# RELAYS.net
KiCad netlist of a schematic drawn in Altium Designer
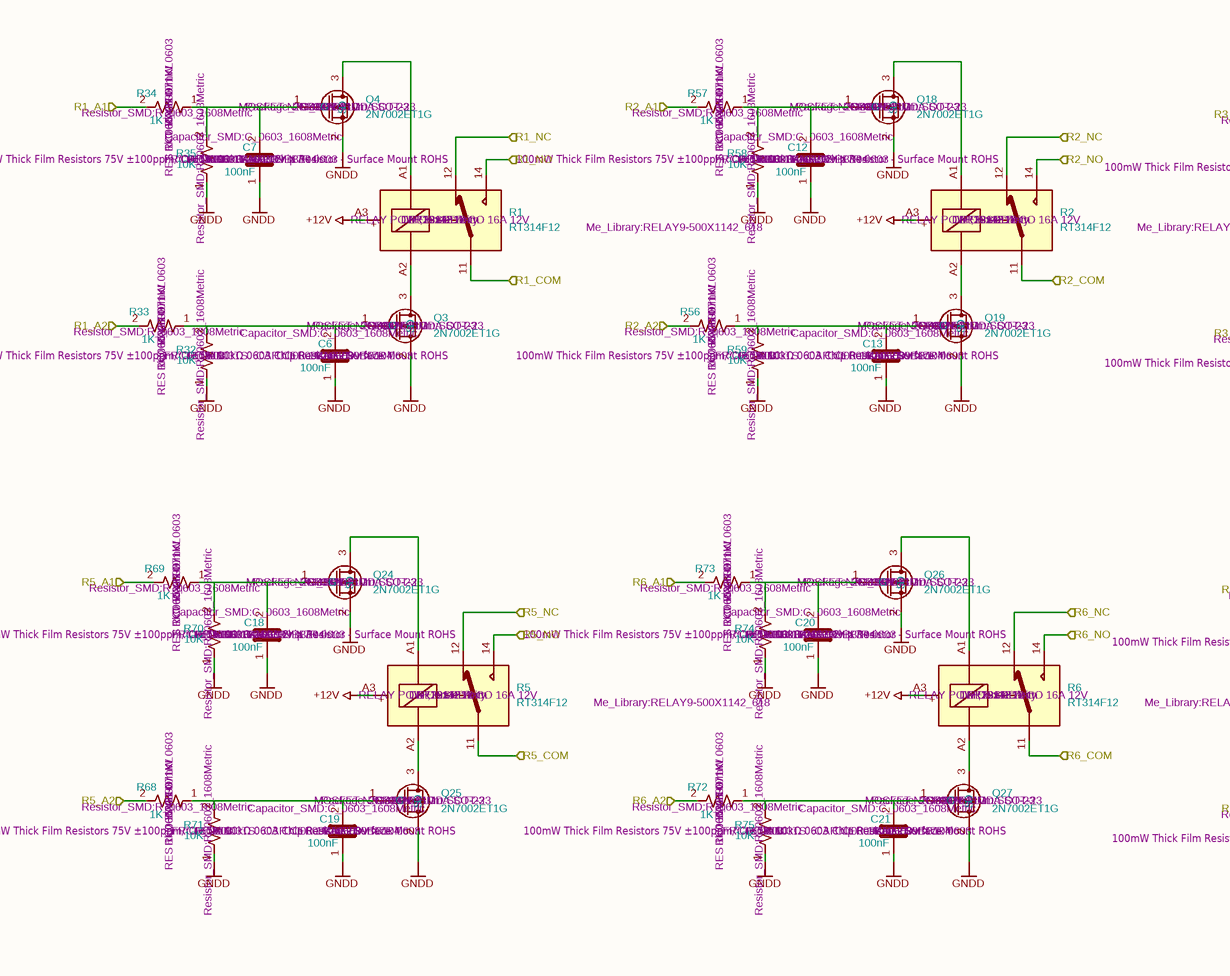
[diagram p0: RELAYS.SchDoc, left]
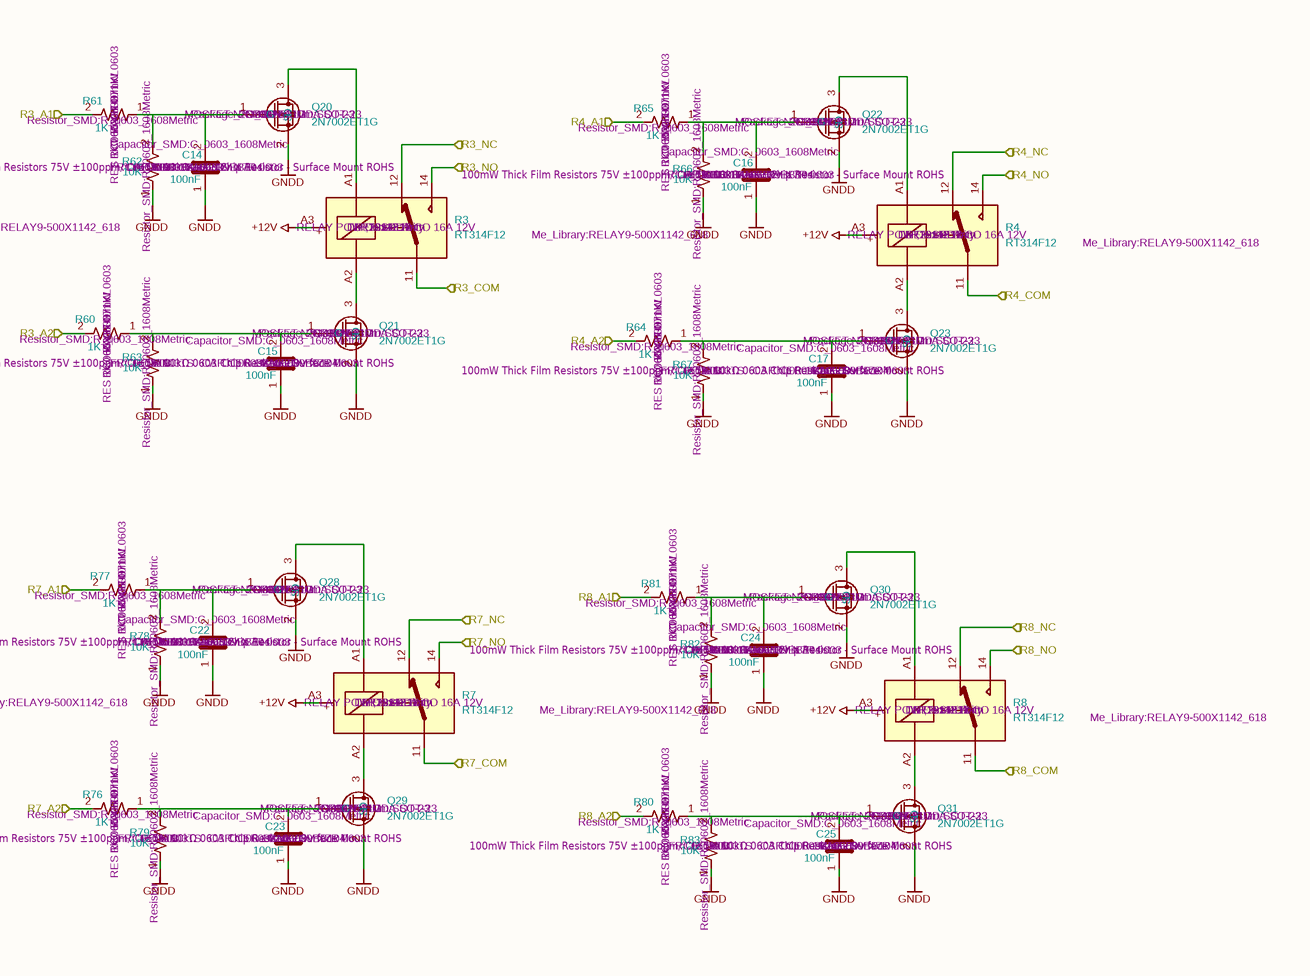
[diagram p1: RELAYS.SchDoc, right]

(export (version "E")
  (design (tool "Eeschema 10.0.6"))
  (components
    (comp (ref "C6")
      (value "100nF")
      (footprint "Capacitor_SMD:C_0603_1608Metric")
      (description "CAP CER 100nF 50V X7R 0603")
      (fields
        (field (name "MP") "CC0603KRX7R9BB104")
        (field (name "MF") "YAGEO")
        (field (name "PACKAGE") "C_0603")
      )
      (libsource (lib "*") (part "C_3"))
    )
    (comp (ref "C7")
      (value "100nF")
      (footprint "Capacitor_SMD:C_0603_1608Metric")
      (description "CAP CER 100nF 50V X7R 0603")
      (fields
        (field (name "MP") "CC0603KRX7R9BB104")
        (field (name "MF") "YAGEO")
        (field (name "PACKAGE") "C_0603")
      )
      (libsource (lib "*") (part "C_3"))
    )
    (comp (ref "C12")
      (value "100nF")
      (footprint "Capacitor_SMD:C_0603_1608Metric")
      (description "CAP CER 100nF 50V X7R 0603")
      (fields
        (field (name "MP") "CC0603KRX7R9BB104")
        (field (name "MF") "YAGEO")
        (field (name "PACKAGE") "C_0603")
      )
      (libsource (lib "*") (part "C_3"))
    )
    (comp (ref "C13")
      (value "100nF")
      (footprint "Capacitor_SMD:C_0603_1608Metric")
      (description "CAP CER 100nF 50V X7R 0603")
      (fields
        (field (name "MP") "CC0603KRX7R9BB104")
        (field (name "MF") "YAGEO")
        (field (name "PACKAGE") "C_0603")
      )
      (libsource (lib "*") (part "C_3"))
    )
    (comp (ref "C14")
      (value "100nF")
      (footprint "Capacitor_SMD:C_0603_1608Metric")
      (description "CAP CER 100nF 50V X7R 0603")
      (fields
        (field (name "MP") "CC0603KRX7R9BB104")
        (field (name "MF") "YAGEO")
        (field (name "PACKAGE") "C_0603")
      )
      (libsource (lib "*") (part "C_3"))
    )
    (comp (ref "C15")
      (value "100nF")
      (footprint "Capacitor_SMD:C_0603_1608Metric")
      (description "CAP CER 100nF 50V X7R 0603")
      (fields
        (field (name "MP") "CC0603KRX7R9BB104")
        (field (name "MF") "YAGEO")
        (field (name "PACKAGE") "C_0603")
      )
      (libsource (lib "*") (part "C_3"))
    )
    (comp (ref "C16")
      (value "100nF")
      (footprint "Capacitor_SMD:C_0603_1608Metric")
      (description "CAP CER 100nF 50V X7R 0603")
      (fields
        (field (name "MP") "CC0603KRX7R9BB104")
        (field (name "MF") "YAGEO")
        (field (name "PACKAGE") "C_0603")
      )
      (libsource (lib "*") (part "C_3"))
    )
    (comp (ref "C17")
      (value "100nF")
      (footprint "Capacitor_SMD:C_0603_1608Metric")
      (description "CAP CER 100nF 50V X7R 0603")
      (fields
        (field (name "MP") "CC0603KRX7R9BB104")
        (field (name "MF") "YAGEO")
        (field (name "PACKAGE") "C_0603")
      )
      (libsource (lib "*") (part "C_3"))
    )
    (comp (ref "C18")
      (value "100nF")
      (footprint "Capacitor_SMD:C_0603_1608Metric")
      (description "CAP CER 100nF 50V X7R 0603")
      (fields
        (field (name "MP") "CC0603KRX7R9BB104")
        (field (name "MF") "YAGEO")
        (field (name "PACKAGE") "C_0603")
      )
      (libsource (lib "*") (part "C_3"))
    )
    (comp (ref "C19")
      (value "100nF")
      (footprint "Capacitor_SMD:C_0603_1608Metric")
      (description "CAP CER 100nF 50V X7R 0603")
      (fields
        (field (name "MP") "CC0603KRX7R9BB104")
        (field (name "MF") "YAGEO")
        (field (name "PACKAGE") "C_0603")
      )
      (libsource (lib "*") (part "C_3"))
    )
    (comp (ref "C20")
      (value "100nF")
      (footprint "Capacitor_SMD:C_0603_1608Metric")
      (description "CAP CER 100nF 50V X7R 0603")
      (fields
        (field (name "MP") "CC0603KRX7R9BB104")
        (field (name "MF") "YAGEO")
        (field (name "PACKAGE") "C_0603")
      )
      (libsource (lib "*") (part "C_3"))
    )
    (comp (ref "C21")
      (value "100nF")
      (footprint "Capacitor_SMD:C_0603_1608Metric")
      (description "CAP CER 100nF 50V X7R 0603")
      (fields
        (field (name "MP") "CC0603KRX7R9BB104")
        (field (name "MF") "YAGEO")
        (field (name "PACKAGE") "C_0603")
      )
      (libsource (lib "*") (part "C_3"))
    )
    (comp (ref "C22")
      (value "100nF")
      (footprint "Capacitor_SMD:C_0603_1608Metric")
      (description "CAP CER 100nF 50V X7R 0603")
      (fields
        (field (name "MP") "CC0603KRX7R9BB104")
        (field (name "MF") "YAGEO")
        (field (name "PACKAGE") "C_0603")
      )
      (libsource (lib "*") (part "C_3"))
    )
    (comp (ref "C23")
      (value "100nF")
      (footprint "Capacitor_SMD:C_0603_1608Metric")
      (description "CAP CER 100nF 50V X7R 0603")
      (fields
        (field (name "MP") "CC0603KRX7R9BB104")
        (field (name "MF") "YAGEO")
        (field (name "PACKAGE") "C_0603")
      )
      (libsource (lib "*") (part "C_3"))
    )
    (comp (ref "C24")
      (value "100nF")
      (footprint "Capacitor_SMD:C_0603_1608Metric")
      (description "CAP CER 100nF 50V X7R 0603")
      (fields
        (field (name "MP") "CC0603KRX7R9BB104")
        (field (name "MF") "YAGEO")
        (field (name "PACKAGE") "C_0603")
      )
      (libsource (lib "*") (part "C_3"))
    )
    (comp (ref "C25")
      (value "100nF")
      (footprint "Capacitor_SMD:C_0603_1608Metric")
      (description "CAP CER 100nF 50V X7R 0603")
      (fields
        (field (name "MP") "CC0603KRX7R9BB104")
        (field (name "MF") "YAGEO")
        (field (name "PACKAGE") "C_0603")
      )
      (libsource (lib "*") (part "C_3"))
    )
    (comp (ref "Q3")
      (value "2N7002ET1G")
      (footprint "Package_TO_SOT_SMD:SOT-23")
      (description "MOSFET N-CH 60V 310mA SOT-23")
      (fields
        (field (name "MP") "2N7002ET1G")
        (field (name "MF") "onsemi")
        (field (name "PACKAGE") "SOT-23")
        (field (name "OZD") "2N7002ET1G")
      )
      (libsource (lib "Transistor_FET_Other") (part "Q_NMOS_Depletion_GSD"))
    )
    (comp (ref "Q4")
      (value "2N7002ET1G")
      (footprint "Package_TO_SOT_SMD:SOT-23")
      (description "MOSFET N-CH 60V 310mA SOT-23")
      (fields
        (field (name "MP") "2N7002ET1G")
        (field (name "MF") "onsemi")
        (field (name "PACKAGE") "SOT-23")
        (field (name "OZD") "2N7002ET1G")
      )
      (libsource (lib "Transistor_FET_Other") (part "Q_NMOS_Depletion_GSD"))
    )
    (comp (ref "Q18")
      (value "2N7002ET1G")
      (footprint "Package_TO_SOT_SMD:SOT-23")
      (description "MOSFET N-CH 60V 310mA SOT-23")
      (fields
        (field (name "MP") "2N7002ET1G")
        (field (name "MF") "onsemi")
        (field (name "PACKAGE") "SOT-23")
        (field (name "OZD") "2N7002ET1G")
      )
      (libsource (lib "Transistor_FET_Other") (part "Q_NMOS_Depletion_GSD"))
    )
    (comp (ref "Q19")
      (value "2N7002ET1G")
      (footprint "Package_TO_SOT_SMD:SOT-23")
      (description "MOSFET N-CH 60V 310mA SOT-23")
      (fields
        (field (name "MP") "2N7002ET1G")
        (field (name "MF") "onsemi")
        (field (name "PACKAGE") "SOT-23")
        (field (name "OZD") "2N7002ET1G")
      )
      (libsource (lib "Transistor_FET_Other") (part "Q_NMOS_Depletion_GSD"))
    )
    (comp (ref "Q20")
      (value "2N7002ET1G")
      (footprint "Package_TO_SOT_SMD:SOT-23")
      (description "MOSFET N-CH 60V 310mA SOT-23")
      (fields
        (field (name "MP") "2N7002ET1G")
        (field (name "MF") "onsemi")
        (field (name "PACKAGE") "SOT-23")
        (field (name "OZD") "2N7002ET1G")
      )
      (libsource (lib "Transistor_FET_Other") (part "Q_NMOS_Depletion_GSD"))
    )
    (comp (ref "Q21")
      (value "2N7002ET1G")
      (footprint "Package_TO_SOT_SMD:SOT-23")
      (description "MOSFET N-CH 60V 310mA SOT-23")
      (fields
        (field (name "MP") "2N7002ET1G")
        (field (name "MF") "onsemi")
        (field (name "PACKAGE") "SOT-23")
        (field (name "OZD") "2N7002ET1G")
      )
      (libsource (lib "Transistor_FET_Other") (part "Q_NMOS_Depletion_GSD"))
    )
    (comp (ref "Q22")
      (value "2N7002ET1G")
      (footprint "Package_TO_SOT_SMD:SOT-23")
      (description "MOSFET N-CH 60V 310mA SOT-23")
      (fields
        (field (name "MP") "2N7002ET1G")
        (field (name "MF") "onsemi")
        (field (name "PACKAGE") "SOT-23")
        (field (name "OZD") "2N7002ET1G")
      )
      (libsource (lib "Transistor_FET_Other") (part "Q_NMOS_Depletion_GSD"))
    )
    (comp (ref "Q23")
      (value "2N7002ET1G")
      (footprint "Package_TO_SOT_SMD:SOT-23")
      (description "MOSFET N-CH 60V 310mA SOT-23")
      (fields
        (field (name "MP") "2N7002ET1G")
        (field (name "MF") "onsemi")
        (field (name "PACKAGE") "SOT-23")
        (field (name "OZD") "2N7002ET1G")
      )
      (libsource (lib "Transistor_FET_Other") (part "Q_NMOS_Depletion_GSD"))
    )
    (comp (ref "Q24")
      (value "2N7002ET1G")
      (footprint "Package_TO_SOT_SMD:SOT-23")
      (description "MOSFET N-CH 60V 310mA SOT-23")
      (fields
        (field (name "MP") "2N7002ET1G")
        (field (name "MF") "onsemi")
        (field (name "PACKAGE") "SOT-23")
        (field (name "OZD") "2N7002ET1G")
      )
      (libsource (lib "Transistor_FET_Other") (part "Q_NMOS_Depletion_GSD"))
    )
    (comp (ref "Q25")
      (value "2N7002ET1G")
      (footprint "Package_TO_SOT_SMD:SOT-23")
      (description "MOSFET N-CH 60V 310mA SOT-23")
      (fields
        (field (name "MP") "2N7002ET1G")
        (field (name "MF") "onsemi")
        (field (name "PACKAGE") "SOT-23")
        (field (name "OZD") "2N7002ET1G")
      )
      (libsource (lib "Transistor_FET_Other") (part "Q_NMOS_Depletion_GSD"))
    )
    (comp (ref "Q26")
      (value "2N7002ET1G")
      (footprint "Package_TO_SOT_SMD:SOT-23")
      (description "MOSFET N-CH 60V 310mA SOT-23")
      (fields
        (field (name "MP") "2N7002ET1G")
        (field (name "MF") "onsemi")
        (field (name "PACKAGE") "SOT-23")
        (field (name "OZD") "2N7002ET1G")
      )
      (libsource (lib "Transistor_FET_Other") (part "Q_NMOS_Depletion_GSD"))
    )
    (comp (ref "Q27")
      (value "2N7002ET1G")
      (footprint "Package_TO_SOT_SMD:SOT-23")
      (description "MOSFET N-CH 60V 310mA SOT-23")
      (fields
        (field (name "MP") "2N7002ET1G")
        (field (name "MF") "onsemi")
        (field (name "PACKAGE") "SOT-23")
        (field (name "OZD") "2N7002ET1G")
      )
      (libsource (lib "Transistor_FET_Other") (part "Q_NMOS_Depletion_GSD"))
    )
    (comp (ref "Q28")
      (value "2N7002ET1G")
      (footprint "Package_TO_SOT_SMD:SOT-23")
      (description "MOSFET N-CH 60V 310mA SOT-23")
      (fields
        (field (name "MP") "2N7002ET1G")
        (field (name "MF") "onsemi")
        (field (name "PACKAGE") "SOT-23")
        (field (name "OZD") "2N7002ET1G")
      )
      (libsource (lib "Transistor_FET_Other") (part "Q_NMOS_Depletion_GSD"))
    )
    (comp (ref "Q29")
      (value "2N7002ET1G")
      (footprint "Package_TO_SOT_SMD:SOT-23")
      (description "MOSFET N-CH 60V 310mA SOT-23")
      (fields
        (field (name "MP") "2N7002ET1G")
        (field (name "MF") "onsemi")
        (field (name "PACKAGE") "SOT-23")
        (field (name "OZD") "2N7002ET1G")
      )
      (libsource (lib "Transistor_FET_Other") (part "Q_NMOS_Depletion_GSD"))
    )
    (comp (ref "Q30")
      (value "2N7002ET1G")
      (footprint "Package_TO_SOT_SMD:SOT-23")
      (description "MOSFET N-CH 60V 310mA SOT-23")
      (fields
        (field (name "MP") "2N7002ET1G")
        (field (name "MF") "onsemi")
        (field (name "PACKAGE") "SOT-23")
        (field (name "OZD") "2N7002ET1G")
      )
      (libsource (lib "Transistor_FET_Other") (part "Q_NMOS_Depletion_GSD"))
    )
    (comp (ref "Q31")
      (value "2N7002ET1G")
      (footprint "Package_TO_SOT_SMD:SOT-23")
      (description "MOSFET N-CH 60V 310mA SOT-23")
      (fields
        (field (name "MP") "2N7002ET1G")
        (field (name "MF") "onsemi")
        (field (name "PACKAGE") "SOT-23")
        (field (name "OZD") "2N7002ET1G")
      )
      (libsource (lib "Transistor_FET_Other") (part "Q_NMOS_Depletion_GSD"))
    )
    (comp (ref "R1")
      (value "RT314F12")
      (footprint "Me_Library:RELAY9-500X1142_618")
      (description "RELAY POWER SPDT-CO 16A 12V")
      (fields
        (field (name "MP") "RT314F12")
        (field (name "MF") "TE Connectivity")
        (field (name "PACKAGE") "DIP,29x12.7mm")
        (field (name "OZD") "RT314F12")
      )
      (libsource (lib "Me_Library") (part "RT314A03"))
    )
    (comp (ref "R2")
      (value "RT314F12")
      (footprint "Me_Library:RELAY9-500X1142_618")
      (description "RELAY POWER SPDT-CO 16A 12V")
      (fields
        (field (name "MP") "RT314F12")
        (field (name "MF") "TE Connectivity")
        (field (name "PACKAGE") "DIP,29x12.7mm")
        (field (name "OZD") "RT314F12")
      )
      (libsource (lib "Me_Library") (part "RT314A03"))
    )
    (comp (ref "R3")
      (value "RT314F12")
      (footprint "Me_Library:RELAY9-500X1142_618")
      (description "RELAY POWER SPDT-CO 16A 12V")
      (fields
        (field (name "MP") "RT314F12")
        (field (name "MF") "TE Connectivity")
        (field (name "PACKAGE") "DIP,29x12.7mm")
        (field (name "OZD") "RT314F12")
      )
      (libsource (lib "Me_Library") (part "RT314A03"))
    )
    (comp (ref "R4")
      (value "RT314F12")
      (footprint "Me_Library:RELAY9-500X1142_618")
      (description "RELAY POWER SPDT-CO 16A 12V")
      (fields
        (field (name "MP") "RT314F12")
        (field (name "MF") "TE Connectivity")
        (field (name "PACKAGE") "DIP,29x12.7mm")
        (field (name "OZD") "RT314F12")
      )
      (libsource (lib "Me_Library") (part "RT314A03"))
    )
    (comp (ref "R5")
      (value "RT314F12")
      (footprint "Me_Library:RELAY9-500X1142_618")
      (description "RELAY POWER SPDT-CO 16A 12V")
      (fields
        (field (name "MP") "RT314F12")
        (field (name "MF") "TE Connectivity")
        (field (name "PACKAGE") "DIP,29x12.7mm")
        (field (name "OZD") "RT314F12")
      )
      (libsource (lib "Me_Library") (part "RT314A03"))
    )
    (comp (ref "R6")
      (value "RT314F12")
      (footprint "Me_Library:RELAY9-500X1142_618")
      (description "RELAY POWER SPDT-CO 16A 12V")
      (fields
        (field (name "MP") "RT314F12")
        (field (name "MF") "TE Connectivity")
        (field (name "PACKAGE") "DIP,29x12.7mm")
        (field (name "OZD") "RT314F12")
      )
      (libsource (lib "Me_Library") (part "RT314A03"))
    )
    (comp (ref "R7")
      (value "RT314F12")
      (footprint "Me_Library:RELAY9-500X1142_618")
      (description "RELAY POWER SPDT-CO 16A 12V")
      (fields
        (field (name "MP") "RT314F12")
        (field (name "MF") "TE Connectivity")
        (field (name "PACKAGE") "DIP,29x12.7mm")
        (field (name "OZD") "RT314F12")
      )
      (libsource (lib "Me_Library") (part "RT314A03"))
    )
    (comp (ref "R8")
      (value "RT314F12")
      (footprint "Me_Library:RELAY9-500X1142_618")
      (description "RELAY POWER SPDT-CO 16A 12V")
      (fields
        (field (name "MP") "RT314F12")
        (field (name "MF") "TE Connectivity")
        (field (name "PACKAGE") "DIP,29x12.7mm")
        (field (name "OZD") "RT314F12")
      )
      (libsource (lib "Me_Library") (part "RT314A03"))
    )
    (comp (ref "R32")
      (value "10K")
      (footprint "Resistor_SMD:R_0603_1608Metric")
      (description "100mW Thick Film Resistors 75V ±100ppm/℃ ±5% 10kΩ 0603 Chip Resistor - Surface Mount ROHS")
      (fields
        (field (name "MP") "FRC0603J103TS")
        (field (name "MF") "FOJAN")
        (field (name "PACKAGE") "R_0603")
      )
      (libsource (lib "Device") (part "R_US"))
    )
    (comp (ref "R33")
      (value "1K")
      (footprint "Resistor_SMD:R_0603_1608Metric")
      (description "RES 1kΩ ±5% 100mW 0603")
      (fields
        (field (name "MP") "RC0603JR-071KL")
        (field (name "MF") "YAGEO")
        (field (name "PACKAGE") "R_0603")
        (field (name "OZD") "RC0603JR-071KL")
      )
      (libsource (lib "Device") (part "R_US"))
    )
    (comp (ref "R34")
      (value "1K")
      (footprint "Resistor_SMD:R_0603_1608Metric")
      (description "RES 1kΩ ±5% 100mW 0603")
      (fields
        (field (name "MP") "RC0603JR-071KL")
        (field (name "MF") "YAGEO")
        (field (name "PACKAGE") "R_0603")
        (field (name "OZD") "RC0603JR-071KL")
      )
      (libsource (lib "Device") (part "R_US"))
    )
    (comp (ref "R35")
      (value "10K")
      (footprint "Resistor_SMD:R_0603_1608Metric")
      (description "100mW Thick Film Resistors 75V ±100ppm/℃ ±5% 10kΩ 0603 Chip Resistor - Surface Mount ROHS")
      (fields
        (field (name "MP") "FRC0603J103TS")
        (field (name "MF") "FOJAN")
        (field (name "PACKAGE") "R_0603")
      )
      (libsource (lib "Device") (part "R_US"))
    )
    (comp (ref "R56")
      (value "1K")
      (footprint "Resistor_SMD:R_0603_1608Metric")
      (description "RES 1kΩ ±5% 100mW 0603")
      (fields
        (field (name "MP") "RC0603JR-071KL")
        (field (name "MF") "YAGEO")
        (field (name "PACKAGE") "R_0603")
        (field (name "OZD") "RC0603JR-071KL")
      )
      (libsource (lib "Device") (part "R_US"))
    )
    (comp (ref "R57")
      (value "1K")
      (footprint "Resistor_SMD:R_0603_1608Metric")
      (description "RES 1kΩ ±5% 100mW 0603")
      (fields
        (field (name "MP") "RC0603JR-071KL")
        (field (name "MF") "YAGEO")
        (field (name "PACKAGE") "R_0603")
        (field (name "OZD") "RC0603JR-071KL")
      )
      (libsource (lib "Device") (part "R_US"))
    )
    (comp (ref "R58")
      (value "10K")
      (footprint "Resistor_SMD:R_0603_1608Metric")
      (description "100mW Thick Film Resistors 75V ±100ppm/℃ ±5% 10kΩ 0603 Chip Resistor - Surface Mount ROHS")
      (fields
        (field (name "MP") "FRC0603J103TS")
        (field (name "MF") "FOJAN")
        (field (name "PACKAGE") "R_0603")
      )
      (libsource (lib "Device") (part "R_US"))
    )
    (comp (ref "R59")
      (value "10K")
      (footprint "Resistor_SMD:R_0603_1608Metric")
      (description "100mW Thick Film Resistors 75V ±100ppm/℃ ±5% 10kΩ 0603 Chip Resistor - Surface Mount ROHS")
      (fields
        (field (name "MP") "FRC0603J103TS")
        (field (name "MF") "FOJAN")
        (field (name "PACKAGE") "R_0603")
      )
      (libsource (lib "Device") (part "R_US"))
    )
    (comp (ref "R60")
      (value "1K")
      (footprint "Resistor_SMD:R_0603_1608Metric")
      (description "RES 1kΩ ±5% 100mW 0603")
      (fields
        (field (name "MP") "RC0603JR-071KL")
        (field (name "MF") "YAGEO")
        (field (name "PACKAGE") "R_0603")
        (field (name "OZD") "RC0603JR-071KL")
      )
      (libsource (lib "Device") (part "R_US"))
    )
    (comp (ref "R61")
      (value "1K")
      (footprint "Resistor_SMD:R_0603_1608Metric")
      (description "RES 1kΩ ±5% 100mW 0603")
      (fields
        (field (name "MP") "RC0603JR-071KL")
        (field (name "MF") "YAGEO")
        (field (name "PACKAGE") "R_0603")
        (field (name "OZD") "RC0603JR-071KL")
      )
      (libsource (lib "Device") (part "R_US"))
    )
    (comp (ref "R62")
      (value "10K")
      (footprint "Resistor_SMD:R_0603_1608Metric")
      (description "100mW Thick Film Resistors 75V ±100ppm/℃ ±5% 10kΩ 0603 Chip Resistor - Surface Mount ROHS")
      (fields
        (field (name "MP") "FRC0603J103TS")
        (field (name "MF") "FOJAN")
        (field (name "PACKAGE") "R_0603")
      )
      (libsource (lib "Device") (part "R_US"))
    )
    (comp (ref "R63")
      (value "10K")
      (footprint "Resistor_SMD:R_0603_1608Metric")
      (description "100mW Thick Film Resistors 75V ±100ppm/℃ ±5% 10kΩ 0603 Chip Resistor - Surface Mount ROHS")
      (fields
        (field (name "MP") "FRC0603J103TS")
        (field (name "MF") "FOJAN")
        (field (name "PACKAGE") "R_0603")
      )
      (libsource (lib "Device") (part "R_US"))
    )
    (comp (ref "R64")
      (value "1K")
      (footprint "Resistor_SMD:R_0603_1608Metric")
      (description "RES 1kΩ ±5% 100mW 0603")
      (fields
        (field (name "MP") "RC0603JR-071KL")
        (field (name "MF") "YAGEO")
        (field (name "PACKAGE") "R_0603")
        (field (name "OZD") "RC0603JR-071KL")
      )
      (libsource (lib "Device") (part "R_US"))
    )
    (comp (ref "R65")
      (value "1K")
      (footprint "Resistor_SMD:R_0603_1608Metric")
      (description "RES 1kΩ ±5% 100mW 0603")
      (fields
        (field (name "MP") "RC0603JR-071KL")
        (field (name "MF") "YAGEO")
        (field (name "PACKAGE") "R_0603")
        (field (name "OZD") "RC0603JR-071KL")
      )
      (libsource (lib "Device") (part "R_US"))
    )
    (comp (ref "R66")
      (value "10K")
      (footprint "Resistor_SMD:R_0603_1608Metric")
      (description "100mW Thick Film Resistors 75V ±100ppm/℃ ±5% 10kΩ 0603 Chip Resistor - Surface Mount ROHS")
      (fields
        (field (name "MP") "FRC0603J103TS")
        (field (name "MF") "FOJAN")
        (field (name "PACKAGE") "R_0603")
      )
      (libsource (lib "Device") (part "R_US"))
    )
    (comp (ref "R67")
      (value "10K")
      (footprint "Resistor_SMD:R_0603_1608Metric")
      (description "100mW Thick Film Resistors 75V ±100ppm/℃ ±5% 10kΩ 0603 Chip Resistor - Surface Mount ROHS")
      (fields
        (field (name "MP") "FRC0603J103TS")
        (field (name "MF") "FOJAN")
        (field (name "PACKAGE") "R_0603")
      )
      (libsource (lib "Device") (part "R_US"))
    )
    (comp (ref "R68")
      (value "1K")
      (footprint "Resistor_SMD:R_0603_1608Metric")
      (description "RES 1kΩ ±5% 100mW 0603")
      (fields
        (field (name "MP") "RC0603JR-071KL")
        (field (name "MF") "YAGEO")
        (field (name "PACKAGE") "R_0603")
        (field (name "OZD") "RC0603JR-071KL")
      )
      (libsource (lib "Device") (part "R_US"))
    )
    (comp (ref "R69")
      (value "1K")
      (footprint "Resistor_SMD:R_0603_1608Metric")
      (description "RES 1kΩ ±5% 100mW 0603")
      (fields
        (field (name "MP") "RC0603JR-071KL")
        (field (name "MF") "YAGEO")
        (field (name "PACKAGE") "R_0603")
        (field (name "OZD") "RC0603JR-071KL")
      )
      (libsource (lib "Device") (part "R_US"))
    )
    (comp (ref "R70")
      (value "10K")
      (footprint "Resistor_SMD:R_0603_1608Metric")
      (description "100mW Thick Film Resistors 75V ±100ppm/℃ ±5% 10kΩ 0603 Chip Resistor - Surface Mount ROHS")
      (fields
        (field (name "MP") "FRC0603J103TS")
        (field (name "MF") "FOJAN")
        (field (name "PACKAGE") "R_0603")
      )
      (libsource (lib "Device") (part "R_US"))
    )
    (comp (ref "R71")
      (value "10K")
      (footprint "Resistor_SMD:R_0603_1608Metric")
      (description "100mW Thick Film Resistors 75V ±100ppm/℃ ±5% 10kΩ 0603 Chip Resistor - Surface Mount ROHS")
      (fields
        (field (name "MP") "FRC0603J103TS")
        (field (name "MF") "FOJAN")
        (field (name "PACKAGE") "R_0603")
      )
      (libsource (lib "Device") (part "R_US"))
    )
    (comp (ref "R72")
      (value "1K")
      (footprint "Resistor_SMD:R_0603_1608Metric")
      (description "RES 1kΩ ±5% 100mW 0603")
      (fields
        (field (name "MP") "RC0603JR-071KL")
        (field (name "MF") "YAGEO")
        (field (name "PACKAGE") "R_0603")
        (field (name "OZD") "RC0603JR-071KL")
      )
      (libsource (lib "Device") (part "R_US"))
    )
    (comp (ref "R73")
      (value "1K")
      (footprint "Resistor_SMD:R_0603_1608Metric")
      (description "RES 1kΩ ±5% 100mW 0603")
      (fields
        (field (name "MP") "RC0603JR-071KL")
        (field (name "MF") "YAGEO")
        (field (name "PACKAGE") "R_0603")
        (field (name "OZD") "RC0603JR-071KL")
      )
      (libsource (lib "Device") (part "R_US"))
    )
    (comp (ref "R74")
      (value "10K")
      (footprint "Resistor_SMD:R_0603_1608Metric")
      (description "100mW Thick Film Resistors 75V ±100ppm/℃ ±5% 10kΩ 0603 Chip Resistor - Surface Mount ROHS")
      (fields
        (field (name "MP") "FRC0603J103TS")
        (field (name "MF") "FOJAN")
        (field (name "PACKAGE") "R_0603")
      )
      (libsource (lib "Device") (part "R_US"))
    )
    (comp (ref "R75")
      (value "10K")
      (footprint "Resistor_SMD:R_0603_1608Metric")
      (description "100mW Thick Film Resistors 75V ±100ppm/℃ ±5% 10kΩ 0603 Chip Resistor - Surface Mount ROHS")
      (fields
        (field (name "MP") "FRC0603J103TS")
        (field (name "MF") "FOJAN")
        (field (name "PACKAGE") "R_0603")
      )
      (libsource (lib "Device") (part "R_US"))
    )
    (comp (ref "R76")
      (value "1K")
      (footprint "Resistor_SMD:R_0603_1608Metric")
      (description "RES 1kΩ ±5% 100mW 0603")
      (fields
        (field (name "MP") "RC0603JR-071KL")
        (field (name "MF") "YAGEO")
        (field (name "PACKAGE") "R_0603")
        (field (name "OZD") "RC0603JR-071KL")
      )
      (libsource (lib "Device") (part "R_US"))
    )
    (comp (ref "R77")
      (value "1K")
      (footprint "Resistor_SMD:R_0603_1608Metric")
      (description "RES 1kΩ ±5% 100mW 0603")
      (fields
        (field (name "MP") "RC0603JR-071KL")
        (field (name "MF") "YAGEO")
        (field (name "PACKAGE") "R_0603")
        (field (name "OZD") "RC0603JR-071KL")
      )
      (libsource (lib "Device") (part "R_US"))
    )
    (comp (ref "R78")
      (value "10K")
      (footprint "Resistor_SMD:R_0603_1608Metric")
      (description "100mW Thick Film Resistors 75V ±100ppm/℃ ±5% 10kΩ 0603 Chip Resistor - Surface Mount ROHS")
      (fields
        (field (name "MP") "FRC0603J103TS")
        (field (name "MF") "FOJAN")
        (field (name "PACKAGE") "R_0603")
      )
      (libsource (lib "Device") (part "R_US"))
    )
    (comp (ref "R79")
      (value "10K")
      (footprint "Resistor_SMD:R_0603_1608Metric")
      (description "100mW Thick Film Resistors 75V ±100ppm/℃ ±5% 10kΩ 0603 Chip Resistor - Surface Mount ROHS")
      (fields
        (field (name "MP") "FRC0603J103TS")
        (field (name "MF") "FOJAN")
        (field (name "PACKAGE") "R_0603")
      )
      (libsource (lib "Device") (part "R_US"))
    )
    (comp (ref "R80")
      (value "1K")
      (footprint "Resistor_SMD:R_0603_1608Metric")
      (description "RES 1kΩ ±5% 100mW 0603")
      (fields
        (field (name "MP") "RC0603JR-071KL")
        (field (name "MF") "YAGEO")
        (field (name "PACKAGE") "R_0603")
        (field (name "OZD") "RC0603JR-071KL")
      )
      (libsource (lib "Device") (part "R_US"))
    )
    (comp (ref "R81")
      (value "1K")
      (footprint "Resistor_SMD:R_0603_1608Metric")
      (description "RES 1kΩ ±5% 100mW 0603")
      (fields
        (field (name "MP") "RC0603JR-071KL")
        (field (name "MF") "YAGEO")
        (field (name "PACKAGE") "R_0603")
        (field (name "OZD") "RC0603JR-071KL")
      )
      (libsource (lib "Device") (part "R_US"))
    )
    (comp (ref "R82")
      (value "10K")
      (footprint "Resistor_SMD:R_0603_1608Metric")
      (description "100mW Thick Film Resistors 75V ±100ppm/℃ ±5% 10kΩ 0603 Chip Resistor - Surface Mount ROHS")
      (fields
        (field (name "MP") "FRC0603J103TS")
        (field (name "MF") "FOJAN")
        (field (name "PACKAGE") "R_0603")
      )
      (libsource (lib "Device") (part "R_US"))
    )
    (comp (ref "R83")
      (value "10K")
      (footprint "Resistor_SMD:R_0603_1608Metric")
      (description "100mW Thick Film Resistors 75V ±100ppm/℃ ±5% 10kΩ 0603 Chip Resistor - Surface Mount ROHS")
      (fields
        (field (name "MP") "FRC0603J103TS")
        (field (name "MF") "FOJAN")
        (field (name "PACKAGE") "R_0603")
      )
      (libsource (lib "Device") (part "R_US"))
    )
  )
  (nets
    (net (code "1") (name "+12V") (class "Default")
      (node (ref "R1") (pin "A3") (pinfunction "A3_A3") (pintype "passive"))
      (node (ref "R2") (pin "A3") (pinfunction "A3_A3") (pintype "passive"))
      (node (ref "R3") (pin "A3") (pinfunction "A3_A3") (pintype "passive"))
      (node (ref "R4") (pin "A3") (pinfunction "A3_A3") (pintype "passive"))
      (node (ref "R5") (pin "A3") (pinfunction "A3_A3") (pintype "passive"))
      (node (ref "R6") (pin "A3") (pinfunction "A3_A3") (pintype "passive"))
      (node (ref "R7") (pin "A3") (pinfunction "A3_A3") (pintype "passive"))
      (node (ref "R8") (pin "A3") (pinfunction "A3_A3") (pintype "passive"))
    )
    (net (code "2") (name "/R1_A1") (class "Default")
      (node (ref "R34") (pin "2") (pinfunction "2_2") (pintype "passive"))
    )
    (net (code "3") (name "/R1_A2") (class "Default")
      (node (ref "R33") (pin "2") (pinfunction "2_2") (pintype "passive"))
    )
    (net (code "4") (name "/R1_COM") (class "Default")
      (node (ref "R1") (pin "11") (pinfunction "11_11") (pintype "passive"))
    )
    (net (code "5") (name "/R1_NC") (class "Default")
      (node (ref "R1") (pin "12") (pinfunction "12_12") (pintype "passive"))
    )
    (net (code "6") (name "/R1_NO") (class "Default")
      (node (ref "R1") (pin "14") (pinfunction "14_14") (pintype "passive"))
    )
    (net (code "7") (name "/R2_A1") (class "Default")
      (node (ref "R57") (pin "2") (pinfunction "2_2") (pintype "passive"))
    )
    (net (code "8") (name "/R2_A2") (class "Default")
      (node (ref "R56") (pin "2") (pinfunction "2_2") (pintype "passive"))
    )
    (net (code "9") (name "/R2_COM") (class "Default")
      (node (ref "R2") (pin "11") (pinfunction "11_11") (pintype "passive"))
    )
    (net (code "10") (name "/R2_NC") (class "Default")
      (node (ref "R2") (pin "12") (pinfunction "12_12") (pintype "passive"))
    )
    (net (code "11") (name "/R2_NO") (class "Default")
      (node (ref "R2") (pin "14") (pinfunction "14_14") (pintype "passive"))
    )
    (net (code "12") (name "/R3_A1") (class "Default")
      (node (ref "R61") (pin "2") (pinfunction "2_2") (pintype "passive"))
    )
    (net (code "13") (name "/R3_A2") (class "Default")
      (node (ref "R60") (pin "2") (pinfunction "2_2") (pintype "passive"))
    )
    (net (code "14") (name "/R3_COM") (class "Default")
      (node (ref "R3") (pin "11") (pinfunction "11_11") (pintype "passive"))
    )
    (net (code "15") (name "/R3_NC") (class "Default")
      (node (ref "R3") (pin "12") (pinfunction "12_12") (pintype "passive"))
    )
    (net (code "16") (name "/R3_NO") (class "Default")
      (node (ref "R3") (pin "14") (pinfunction "14_14") (pintype "passive"))
    )
    (net (code "17") (name "/R4_A1") (class "Default")
      (node (ref "R65") (pin "2") (pinfunction "2_2") (pintype "passive"))
    )
    (net (code "18") (name "/R4_A2") (class "Default")
      (node (ref "R64") (pin "2") (pinfunction "2_2") (pintype "passive"))
    )
    (net (code "19") (name "/R4_COM") (class "Default")
      (node (ref "R4") (pin "11") (pinfunction "11_11") (pintype "passive"))
    )
    (net (code "20") (name "/R4_NC") (class "Default")
      (node (ref "R4") (pin "12") (pinfunction "12_12") (pintype "passive"))
    )
    (net (code "21") (name "/R4_NO") (class "Default")
      (node (ref "R4") (pin "14") (pinfunction "14_14") (pintype "passive"))
    )
    (net (code "22") (name "/R5_A1") (class "Default")
      (node (ref "R69") (pin "2") (pinfunction "2_2") (pintype "passive"))
    )
    (net (code "23") (name "/R5_A2") (class "Default")
      (node (ref "R68") (pin "2") (pinfunction "2_2") (pintype "passive"))
    )
    (net (code "24") (name "/R5_COM") (class "Default")
      (node (ref "R5") (pin "11") (pinfunction "11_11") (pintype "passive"))
    )
    (net (code "25") (name "/R5_NC") (class "Default")
      (node (ref "R5") (pin "12") (pinfunction "12_12") (pintype "passive"))
    )
    (net (code "26") (name "/R5_NO") (class "Default")
      (node (ref "R5") (pin "14") (pinfunction "14_14") (pintype "passive"))
    )
    (net (code "27") (name "/R6_A1") (class "Default")
      (node (ref "R73") (pin "2") (pinfunction "2_2") (pintype "passive"))
    )
    (net (code "28") (name "/R6_A2") (class "Default")
      (node (ref "R72") (pin "2") (pinfunction "2_2") (pintype "passive"))
    )
    (net (code "29") (name "/R6_COM") (class "Default")
      (node (ref "R6") (pin "11") (pinfunction "11_11") (pintype "passive"))
    )
    (net (code "30") (name "/R6_NC") (class "Default")
      (node (ref "R6") (pin "12") (pinfunction "12_12") (pintype "passive"))
    )
    (net (code "31") (name "/R6_NO") (class "Default")
      (node (ref "R6") (pin "14") (pinfunction "14_14") (pintype "passive"))
    )
    (net (code "32") (name "/R7_A1") (class "Default")
      (node (ref "R77") (pin "2") (pinfunction "2_2") (pintype "passive"))
    )
    (net (code "33") (name "/R7_A2") (class "Default")
      (node (ref "R76") (pin "2") (pinfunction "2_2") (pintype "passive"))
    )
    (net (code "34") (name "/R7_COM") (class "Default")
      (node (ref "R7") (pin "11") (pinfunction "11_11") (pintype "passive"))
    )
    (net (code "35") (name "/R7_NC") (class "Default")
      (node (ref "R7") (pin "12") (pinfunction "12_12") (pintype "passive"))
    )
    (net (code "36") (name "/R7_NO") (class "Default")
      (node (ref "R7") (pin "14") (pinfunction "14_14") (pintype "passive"))
    )
    (net (code "37") (name "/R8_A1") (class "Default")
      (node (ref "R81") (pin "2") (pinfunction "2_2") (pintype "passive"))
    )
    (net (code "38") (name "/R8_A2") (class "Default")
      (node (ref "R80") (pin "2") (pinfunction "2_2") (pintype "passive"))
    )
    (net (code "39") (name "/R8_COM") (class "Default")
      (node (ref "R8") (pin "11") (pinfunction "11_11") (pintype "passive"))
    )
    (net (code "40") (name "/R8_NC") (class "Default")
      (node (ref "R8") (pin "12") (pinfunction "12_12") (pintype "passive"))
    )
    (net (code "41") (name "/R8_NO") (class "Default")
      (node (ref "R8") (pin "14") (pinfunction "14_14") (pintype "passive"))
    )
    (net (code "42") (name "GNDD") (class "Default")
      (node (ref "C12") (pin "1") (pinfunction "1_1") (pintype "passive"))
      (node (ref "C13") (pin "1") (pinfunction "1_1") (pintype "passive"))
      (node (ref "C14") (pin "1") (pinfunction "1_1") (pintype "passive"))
      (node (ref "C15") (pin "1") (pinfunction "1_1") (pintype "passive"))
      (node (ref "C16") (pin "1") (pinfunction "1_1") (pintype "passive"))
      (node (ref "C17") (pin "1") (pinfunction "1_1") (pintype "passive"))
      (node (ref "C18") (pin "1") (pinfunction "1_1") (pintype "passive"))
      (node (ref "C19") (pin "1") (pinfunction "1_1") (pintype "passive"))
      (node (ref "C20") (pin "1") (pinfunction "1_1") (pintype "passive"))
      (node (ref "C21") (pin "1") (pinfunction "1_1") (pintype "passive"))
      (node (ref "C22") (pin "1") (pinfunction "1_1") (pintype "passive"))
      (node (ref "C23") (pin "1") (pinfunction "1_1") (pintype "passive"))
      (node (ref "C24") (pin "1") (pinfunction "1_1") (pintype "passive"))
      (node (ref "C25") (pin "1") (pinfunction "1_1") (pintype "passive"))
      (node (ref "C6") (pin "1") (pinfunction "1_1") (pintype "passive"))
      (node (ref "C7") (pin "1") (pinfunction "1_1") (pintype "passive"))
      (node (ref "Q18") (pin "2") (pinfunction "S_2") (pintype "passive"))
      (node (ref "Q19") (pin "2") (pinfunction "S_2") (pintype "passive"))
      (node (ref "Q20") (pin "2") (pinfunction "S_2") (pintype "passive"))
      (node (ref "Q21") (pin "2") (pinfunction "S_2") (pintype "passive"))
      (node (ref "Q22") (pin "2") (pinfunction "S_2") (pintype "passive"))
      (node (ref "Q23") (pin "2") (pinfunction "S_2") (pintype "passive"))
      (node (ref "Q24") (pin "2") (pinfunction "S_2") (pintype "passive"))
      (node (ref "Q25") (pin "2") (pinfunction "S_2") (pintype "passive"))
      (node (ref "Q26") (pin "2") (pinfunction "S_2") (pintype "passive"))
      (node (ref "Q27") (pin "2") (pinfunction "S_2") (pintype "passive"))
      (node (ref "Q28") (pin "2") (pinfunction "S_2") (pintype "passive"))
      (node (ref "Q29") (pin "2") (pinfunction "S_2") (pintype "passive"))
      (node (ref "Q3") (pin "2") (pinfunction "S_2") (pintype "passive"))
      (node (ref "Q30") (pin "2") (pinfunction "S_2") (pintype "passive"))
      (node (ref "Q31") (pin "2") (pinfunction "S_2") (pintype "passive"))
      (node (ref "Q4") (pin "2") (pinfunction "S_2") (pintype "passive"))
      (node (ref "R32") (pin "1") (pinfunction "1_1") (pintype "passive"))
      (node (ref "R35") (pin "1") (pinfunction "1_1") (pintype "passive"))
      (node (ref "R58") (pin "1") (pinfunction "1_1") (pintype "passive"))
      (node (ref "R59") (pin "1") (pinfunction "1_1") (pintype "passive"))
      (node (ref "R62") (pin "1") (pinfunction "1_1") (pintype "passive"))
      (node (ref "R63") (pin "1") (pinfunction "1_1") (pintype "passive"))
      (node (ref "R66") (pin "1") (pinfunction "1_1") (pintype "passive"))
      (node (ref "R67") (pin "1") (pinfunction "1_1") (pintype "passive"))
      (node (ref "R70") (pin "1") (pinfunction "1_1") (pintype "passive"))
      (node (ref "R71") (pin "1") (pinfunction "1_1") (pintype "passive"))
      (node (ref "R74") (pin "1") (pinfunction "1_1") (pintype "passive"))
      (node (ref "R75") (pin "1") (pinfunction "1_1") (pintype "passive"))
      (node (ref "R78") (pin "1") (pinfunction "1_1") (pintype "passive"))
      (node (ref "R79") (pin "1") (pinfunction "1_1") (pintype "passive"))
      (node (ref "R82") (pin "1") (pinfunction "1_1") (pintype "passive"))
      (node (ref "R83") (pin "1") (pinfunction "1_1") (pintype "passive"))
    )
    (net (code "43") (name "Net-(Q3-D)") (class "Default")
      (node (ref "Q3") (pin "3") (pinfunction "D_3") (pintype "passive"))
      (node (ref "R1") (pin "A2") (pinfunction "A2_A2") (pintype "passive"))
    )
    (net (code "44") (name "Net-(Q3-G)") (class "Default")
      (node (ref "C6") (pin "2") (pinfunction "2_2") (pintype "passive"))
      (node (ref "Q3") (pin "1") (pinfunction "G_1") (pintype "passive"))
      (node (ref "R32") (pin "2") (pinfunction "2_2") (pintype "passive"))
      (node (ref "R33") (pin "1") (pinfunction "1_1") (pintype "passive"))
    )
    (net (code "45") (name "Net-(Q4-D)") (class "Default")
      (node (ref "Q4") (pin "3") (pinfunction "D_3") (pintype "passive"))
      (node (ref "R1") (pin "A1") (pinfunction "A1_A1") (pintype "passive"))
    )
    (net (code "46") (name "Net-(Q4-G)") (class "Default")
      (node (ref "C7") (pin "2") (pinfunction "2_2") (pintype "passive"))
      (node (ref "Q4") (pin "1") (pinfunction "G_1") (pintype "passive"))
      (node (ref "R34") (pin "1") (pinfunction "1_1") (pintype "passive"))
      (node (ref "R35") (pin "2") (pinfunction "2_2") (pintype "passive"))
    )
    (net (code "47") (name "Net-(Q18-D)") (class "Default")
      (node (ref "Q18") (pin "3") (pinfunction "D_3") (pintype "passive"))
      (node (ref "R2") (pin "A1") (pinfunction "A1_A1") (pintype "passive"))
    )
    (net (code "48") (name "Net-(Q18-G)") (class "Default")
      (node (ref "C12") (pin "2") (pinfunction "2_2") (pintype "passive"))
      (node (ref "Q18") (pin "1") (pinfunction "G_1") (pintype "passive"))
      (node (ref "R57") (pin "1") (pinfunction "1_1") (pintype "passive"))
      (node (ref "R58") (pin "2") (pinfunction "2_2") (pintype "passive"))
    )
    (net (code "49") (name "Net-(Q19-D)") (class "Default")
      (node (ref "Q19") (pin "3") (pinfunction "D_3") (pintype "passive"))
      (node (ref "R2") (pin "A2") (pinfunction "A2_A2") (pintype "passive"))
    )
    (net (code "50") (name "Net-(Q19-G)") (class "Default")
      (node (ref "C13") (pin "2") (pinfunction "2_2") (pintype "passive"))
      (node (ref "Q19") (pin "1") (pinfunction "G_1") (pintype "passive"))
      (node (ref "R56") (pin "1") (pinfunction "1_1") (pintype "passive"))
      (node (ref "R59") (pin "2") (pinfunction "2_2") (pintype "passive"))
    )
    (net (code "51") (name "Net-(Q20-D)") (class "Default")
      (node (ref "Q20") (pin "3") (pinfunction "D_3") (pintype "passive"))
      (node (ref "R3") (pin "A1") (pinfunction "A1_A1") (pintype "passive"))
    )
    (net (code "52") (name "Net-(Q20-G)") (class "Default")
      (node (ref "C14") (pin "2") (pinfunction "2_2") (pintype "passive"))
      (node (ref "Q20") (pin "1") (pinfunction "G_1") (pintype "passive"))
      (node (ref "R61") (pin "1") (pinfunction "1_1") (pintype "passive"))
      (node (ref "R62") (pin "2") (pinfunction "2_2") (pintype "passive"))
    )
    (net (code "53") (name "Net-(Q21-D)") (class "Default")
      (node (ref "Q21") (pin "3") (pinfunction "D_3") (pintype "passive"))
      (node (ref "R3") (pin "A2") (pinfunction "A2_A2") (pintype "passive"))
    )
    (net (code "54") (name "Net-(Q21-G)") (class "Default")
      (node (ref "C15") (pin "2") (pinfunction "2_2") (pintype "passive"))
      (node (ref "Q21") (pin "1") (pinfunction "G_1") (pintype "passive"))
      (node (ref "R60") (pin "1") (pinfunction "1_1") (pintype "passive"))
      (node (ref "R63") (pin "2") (pinfunction "2_2") (pintype "passive"))
    )
    (net (code "55") (name "Net-(Q22-D)") (class "Default")
      (node (ref "Q22") (pin "3") (pinfunction "D_3") (pintype "passive"))
      (node (ref "R4") (pin "A1") (pinfunction "A1_A1") (pintype "passive"))
    )
    (net (code "56") (name "Net-(Q22-G)") (class "Default")
      (node (ref "C16") (pin "2") (pinfunction "2_2") (pintype "passive"))
      (node (ref "Q22") (pin "1") (pinfunction "G_1") (pintype "passive"))
      (node (ref "R65") (pin "1") (pinfunction "1_1") (pintype "passive"))
      (node (ref "R66") (pin "2") (pinfunction "2_2") (pintype "passive"))
    )
    (net (code "57") (name "Net-(Q23-D)") (class "Default")
      (node (ref "Q23") (pin "3") (pinfunction "D_3") (pintype "passive"))
      (node (ref "R4") (pin "A2") (pinfunction "A2_A2") (pintype "passive"))
    )
    (net (code "58") (name "Net-(Q23-G)") (class "Default")
      (node (ref "C17") (pin "2") (pinfunction "2_2") (pintype "passive"))
      (node (ref "Q23") (pin "1") (pinfunction "G_1") (pintype "passive"))
      (node (ref "R64") (pin "1") (pinfunction "1_1") (pintype "passive"))
      (node (ref "R67") (pin "2") (pinfunction "2_2") (pintype "passive"))
    )
    (net (code "59") (name "Net-(Q24-D)") (class "Default")
      (node (ref "Q24") (pin "3") (pinfunction "D_3") (pintype "passive"))
      (node (ref "R5") (pin "A1") (pinfunction "A1_A1") (pintype "passive"))
    )
    (net (code "60") (name "Net-(Q24-G)") (class "Default")
      (node (ref "C18") (pin "2") (pinfunction "2_2") (pintype "passive"))
      (node (ref "Q24") (pin "1") (pinfunction "G_1") (pintype "passive"))
      (node (ref "R69") (pin "1") (pinfunction "1_1") (pintype "passive"))
      (node (ref "R70") (pin "2") (pinfunction "2_2") (pintype "passive"))
    )
    (net (code "61") (name "Net-(Q25-D)") (class "Default")
      (node (ref "Q25") (pin "3") (pinfunction "D_3") (pintype "passive"))
      (node (ref "R5") (pin "A2") (pinfunction "A2_A2") (pintype "passive"))
    )
    (net (code "62") (name "Net-(Q25-G)") (class "Default")
      (node (ref "C19") (pin "2") (pinfunction "2_2") (pintype "passive"))
      (node (ref "Q25") (pin "1") (pinfunction "G_1") (pintype "passive"))
      (node (ref "R68") (pin "1") (pinfunction "1_1") (pintype "passive"))
      (node (ref "R71") (pin "2") (pinfunction "2_2") (pintype "passive"))
    )
    (net (code "63") (name "Net-(Q26-D)") (class "Default")
      (node (ref "Q26") (pin "3") (pinfunction "D_3") (pintype "passive"))
      (node (ref "R6") (pin "A1") (pinfunction "A1_A1") (pintype "passive"))
    )
    (net (code "64") (name "Net-(Q26-G)") (class "Default")
      (node (ref "C20") (pin "2") (pinfunction "2_2") (pintype "passive"))
      (node (ref "Q26") (pin "1") (pinfunction "G_1") (pintype "passive"))
      (node (ref "R73") (pin "1") (pinfunction "1_1") (pintype "passive"))
      (node (ref "R74") (pin "2") (pinfunction "2_2") (pintype "passive"))
    )
    (net (code "65") (name "Net-(Q27-D)") (class "Default")
      (node (ref "Q27") (pin "3") (pinfunction "D_3") (pintype "passive"))
      (node (ref "R6") (pin "A2") (pinfunction "A2_A2") (pintype "passive"))
    )
    (net (code "66") (name "Net-(Q27-G)") (class "Default")
      (node (ref "C21") (pin "2") (pinfunction "2_2") (pintype "passive"))
      (node (ref "Q27") (pin "1") (pinfunction "G_1") (pintype "passive"))
      (node (ref "R72") (pin "1") (pinfunction "1_1") (pintype "passive"))
      (node (ref "R75") (pin "2") (pinfunction "2_2") (pintype "passive"))
    )
    (net (code "67") (name "Net-(Q28-D)") (class "Default")
      (node (ref "Q28") (pin "3") (pinfunction "D_3") (pintype "passive"))
      (node (ref "R7") (pin "A1") (pinfunction "A1_A1") (pintype "passive"))
    )
    (net (code "68") (name "Net-(Q28-G)") (class "Default")
      (node (ref "C22") (pin "2") (pinfunction "2_2") (pintype "passive"))
      (node (ref "Q28") (pin "1") (pinfunction "G_1") (pintype "passive"))
      (node (ref "R77") (pin "1") (pinfunction "1_1") (pintype "passive"))
      (node (ref "R78") (pin "2") (pinfunction "2_2") (pintype "passive"))
    )
    (net (code "69") (name "Net-(Q29-D)") (class "Default")
      (node (ref "Q29") (pin "3") (pinfunction "D_3") (pintype "passive"))
      (node (ref "R7") (pin "A2") (pinfunction "A2_A2") (pintype "passive"))
    )
    (net (code "70") (name "Net-(Q29-G)") (class "Default")
      (node (ref "C23") (pin "2") (pinfunction "2_2") (pintype "passive"))
      (node (ref "Q29") (pin "1") (pinfunction "G_1") (pintype "passive"))
      (node (ref "R76") (pin "1") (pinfunction "1_1") (pintype "passive"))
      (node (ref "R79") (pin "2") (pinfunction "2_2") (pintype "passive"))
    )
    (net (code "71") (name "Net-(Q30-D)") (class "Default")
      (node (ref "Q30") (pin "3") (pinfunction "D_3") (pintype "passive"))
      (node (ref "R8") (pin "A1") (pinfunction "A1_A1") (pintype "passive"))
    )
    (net (code "72") (name "Net-(Q30-G)") (class "Default")
      (node (ref "C24") (pin "2") (pinfunction "2_2") (pintype "passive"))
      (node (ref "Q30") (pin "1") (pinfunction "G_1") (pintype "passive"))
      (node (ref "R81") (pin "1") (pinfunction "1_1") (pintype "passive"))
      (node (ref "R82") (pin "2") (pinfunction "2_2") (pintype "passive"))
    )
    (net (code "73") (name "Net-(Q31-D)") (class "Default")
      (node (ref "Q31") (pin "3") (pinfunction "D_3") (pintype "passive"))
      (node (ref "R8") (pin "A2") (pinfunction "A2_A2") (pintype "passive"))
    )
    (net (code "74") (name "Net-(Q31-G)") (class "Default")
      (node (ref "C25") (pin "2") (pinfunction "2_2") (pintype "passive"))
      (node (ref "Q31") (pin "1") (pinfunction "G_1") (pintype "passive"))
      (node (ref "R80") (pin "1") (pinfunction "1_1") (pintype "passive"))
      (node (ref "R83") (pin "2") (pinfunction "2_2") (pintype "passive"))
    )
  )
)
